# PA2_PMIC.net
KiCad netlist of a schematic drawn in Altium Designer
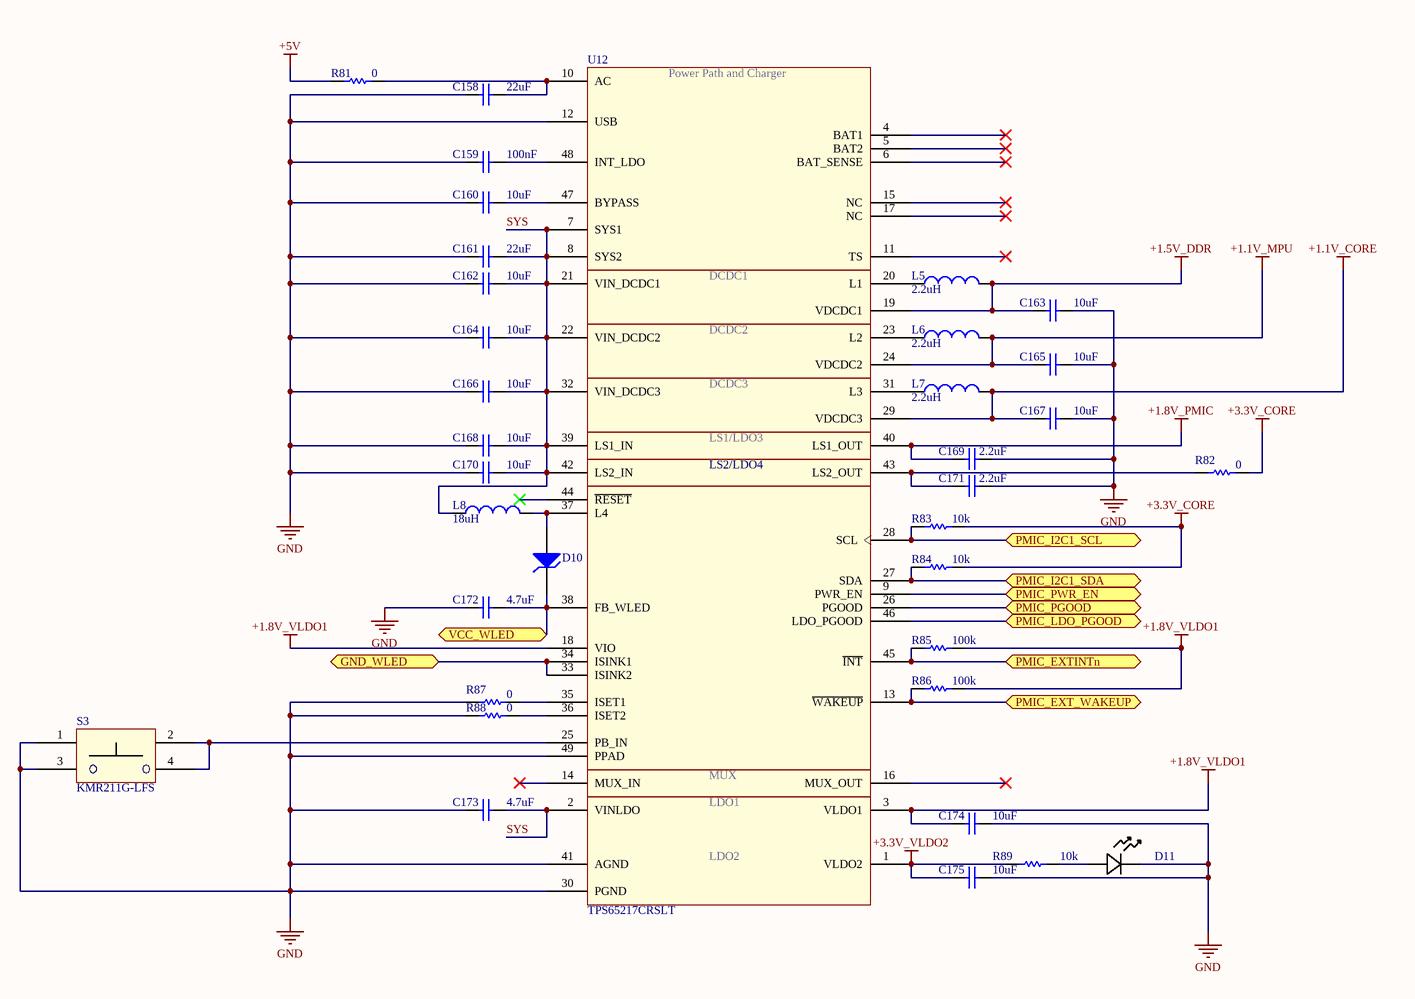
[diagram p0: PA2_PMIC.SchDoc]

(export (version "E")
  (design (tool "Eeschema 10.0.6"))
  (components
    (comp (ref "C158")
      (value "22uF")
      (footprint "CAPC1608X08")
      (description "Capacitor")
      (fields (field (name "Comment") "Cap 22uF"))
      (libsource (lib "Michel") (part "Cap"))
    )
    (comp (ref "C159")
      (value "100nF")
      (footprint "CAPC1608X08")
      (description "Capacitor")
      (fields (field (name "Comment") "Cap 100nF"))
      (libsource (lib "Michel") (part "Cap"))
    )
    (comp (ref "C160")
      (value "10uF")
      (footprint "CAPC1608X08")
      (description "Capacitor")
      (fields (field (name "Comment") "Cap 10uF"))
      (libsource (lib "Michel") (part "Cap"))
    )
    (comp (ref "C161")
      (value "22uF")
      (footprint "CAPC1608X08")
      (description "Capacitor")
      (fields (field (name "Comment") "Cap 22uF"))
      (libsource (lib "Michel") (part "Cap"))
    )
    (comp (ref "C162")
      (value "10uF")
      (footprint "CAPC1608X08")
      (description "Capacitor")
      (fields (field (name "Comment") "Cap 10uF"))
      (libsource (lib "Michel") (part "Cap"))
    )
    (comp (ref "C163")
      (value "10uF")
      (footprint "CAPC1608X08")
      (description "Capacitor")
      (fields (field (name "Comment") "Cap 10uF"))
      (libsource (lib "Michel") (part "Cap"))
    )
    (comp (ref "C164")
      (value "10uF")
      (footprint "CAPC1608X08")
      (description "Capacitor")
      (fields (field (name "Comment") "Cap 10uF"))
      (libsource (lib "Michel") (part "Cap"))
    )
    (comp (ref "C165")
      (value "10uF")
      (footprint "CAPC1608X08")
      (description "Capacitor")
      (fields (field (name "Comment") "Cap 10uF"))
      (libsource (lib "Michel") (part "Cap"))
    )
    (comp (ref "C166")
      (value "10uF")
      (footprint "CAPC1608X08")
      (description "Capacitor")
      (fields (field (name "Comment") "Cap 10uF"))
      (libsource (lib "Michel") (part "Cap"))
    )
    (comp (ref "C167")
      (value "10uF")
      (footprint "CAPC1608X08")
      (description "Capacitor")
      (fields (field (name "Comment") "Cap 10uF"))
      (libsource (lib "Michel") (part "Cap"))
    )
    (comp (ref "C168")
      (value "10uF")
      (footprint "CAPC1608X08")
      (description "Capacitor")
      (fields (field (name "Comment") "Cap 10uF"))
      (libsource (lib "Michel") (part "Cap"))
    )
    (comp (ref "C169")
      (value "2.2uF")
      (footprint "CAPC1608X08")
      (description "Capacitor")
      (fields (field (name "Comment") "Cap 2.2uF"))
      (libsource (lib "Michel") (part "Cap"))
    )
    (comp (ref "C170")
      (value "10uF")
      (footprint "CAPC1608X08")
      (description "Capacitor")
      (fields (field (name "Comment") "Cap 10uF"))
      (libsource (lib "Michel") (part "Cap"))
    )
    (comp (ref "C171")
      (value "2.2uF")
      (footprint "CAPC1608X08")
      (description "Capacitor")
      (fields (field (name "Comment") "Cap 2.2uF"))
      (libsource (lib "Michel") (part "Cap"))
    )
    (comp (ref "C172")
      (value "4.7uF")
      (footprint "CAPC1608X08")
      (description "Capacitor")
      (fields (field (name "Comment") "Cap 4.7uF"))
      (libsource (lib "Michel") (part "Cap"))
    )
    (comp (ref "C173")
      (value "4.7uF")
      (footprint "CAPC1608X08")
      (description "Capacitor")
      (fields (field (name "Comment") "Cap 4.7uF"))
      (libsource (lib "Michel") (part "Cap"))
    )
    (comp (ref "C174")
      (value "10uF")
      (footprint "CAPC1608X08")
      (description "Capacitor")
      (fields (field (name "Comment") "Cap 10uF"))
      (libsource (lib "Michel") (part "Cap"))
    )
    (comp (ref "C175")
      (value "10uF")
      (footprint "CAPC1608X08")
      (description "Capacitor")
      (fields (field (name "Comment") "Cap 10uF"))
      (libsource (lib "Michel") (part "Cap"))
    )
    (comp (ref "D10")
      (value "D Zener")
      (footprint "MF03A-M")
      (description "Zener Diode")
      (libsource (lib "Michel") (part "D Zener"))
    )
    (comp (ref "D11")
      (value "Blanc")
      (footprint "LED_LNJ")
      (description "LED Blanc")
      (libsource (lib "Michel") (part "LNJ037X8ARA"))
    )
    (comp (ref "L5")
      (value "2.2uH")
      (footprint "INDM1608X08N")
      (description "Inductor")
      (libsource (lib "Michel") (part "Inductor"))
    )
    (comp (ref "L6")
      (value "2.2uH")
      (footprint "INDM1608X08N")
      (description "Inductor")
      (libsource (lib "Michel") (part "Inductor"))
    )
    (comp (ref "L7")
      (value "2.2uH")
      (footprint "INDM1608X08N")
      (description "Inductor")
      (libsource (lib "Michel") (part "Inductor"))
    )
    (comp (ref "L8")
      (value "18uH")
      (footprint "INDM2612X12N")
      (description "Inductor")
      (libsource (lib "Michel") (part "Inductor"))
    )
    (comp (ref "R81")
      (value "0")
      (footprint "RESC1608X05")
      (description "Resistor")
      (fields (field (name "Comment") "Res 0 Ohm"))
      (libsource (lib "Michel") (part "Res1"))
    )
    (comp (ref "R82")
      (value "0")
      (footprint "RESC1608X05")
      (description "Resistor")
      (fields (field (name "Comment") "Res 0 Ohm"))
      (libsource (lib "Michel") (part "Res1"))
    )
    (comp (ref "R83")
      (value "10k")
      (footprint "RESC1608X05")
      (description "Resistor")
      (fields (field (name "Comment") "Res 10k"))
      (libsource (lib "Michel") (part "Res1"))
    )
    (comp (ref "R84")
      (value "10k")
      (footprint "RESC1608X05")
      (description "Resistor")
      (fields (field (name "Comment") "Res 10k"))
      (libsource (lib "Michel") (part "Res1"))
    )
    (comp (ref "R85")
      (value "100k")
      (footprint "RESC1608X05")
      (description "Resistor")
      (fields (field (name "Comment") "Res 100k"))
      (libsource (lib "Michel") (part "Res1"))
    )
    (comp (ref "R86")
      (value "100k")
      (footprint "RESC1608X05")
      (description "Resistor")
      (fields (field (name "Comment") "Res 100k"))
      (libsource (lib "Michel") (part "Res1"))
    )
    (comp (ref "R87")
      (value "0")
      (footprint "RESC1608X05")
      (description "Resistor")
      (fields (field (name "Comment") "Res 0 Ohm"))
      (libsource (lib "Michel") (part "Res1"))
    )
    (comp (ref "R88")
      (value "0")
      (footprint "RESC1608X05")
      (description "Resistor")
      (fields (field (name "Comment") "Res 0 Ohm"))
      (libsource (lib "Michel") (part "Res1"))
    )
    (comp (ref "R89")
      (value "10k")
      (footprint "RESC1608X05")
      (description "Resistor")
      (fields (field (name "Comment") "Res 10k"))
      (libsource (lib "Michel") (part "Res1"))
    )
    (comp (ref "S3")
      (value "KMR211G-LFS")
      (footprint "C&K_KMR211G")
      (description "Commutateur tactile")
      (libsource (lib "Michel") (part "KMR211G-LFS"))
    )
    (comp (ref "U12")
      (value "TPS65217CRSLT")
      (footprint "CRSLT")
      (description "Gestion d'alimentation PMIC")
      (libsource (lib "Michel") (part "TPS65217CRSLT"))
    )
  )
  (nets
    (net (code "1") (name "+1.1V_CORE") (class "Default")
      (node (ref "C167") (pin "1") (pinfunction "1_1") (pintype "passive"))
      (node (ref "L7") (pin "2") (pinfunction "2_2") (pintype "passive"))
      (node (ref "U12") (pin "29") (pinfunction "VDCDC3_29") (pintype "passive"))
    )
    (net (code "2") (name "+1.1V_MPU") (class "Default")
      (node (ref "C165") (pin "1") (pinfunction "1_1") (pintype "passive"))
      (node (ref "L6") (pin "2") (pinfunction "2_2") (pintype "passive"))
      (node (ref "U12") (pin "24") (pinfunction "VDCDC2_24") (pintype "passive"))
    )
    (net (code "3") (name "+1.5V_DDR") (class "Default")
      (node (ref "C163") (pin "1") (pinfunction "1_1") (pintype "passive"))
      (node (ref "L5") (pin "2") (pinfunction "2_2") (pintype "passive"))
      (node (ref "U12") (pin "19") (pinfunction "VDCDC1_19") (pintype "passive"))
    )
    (net (code "4") (name "+1.8V_PMIC") (class "Default")
      (node (ref "C169") (pin "2") (pinfunction "2_2") (pintype "passive"))
      (node (ref "U12") (pin "40") (pinfunction "LS1_OUT_40") (pintype "passive"))
    )
    (net (code "5") (name "+1.8V_VLDO1") (class "Default")
      (node (ref "C174") (pin "1") (pinfunction "1_1") (pintype "passive"))
      (node (ref "R85") (pin "2") (pinfunction "2_2") (pintype "passive"))
      (node (ref "R86") (pin "2") (pinfunction "2_2") (pintype "passive"))
      (node (ref "U12") (pin "18") (pinfunction "VIO_18") (pintype "passive"))
      (node (ref "U12") (pin "3") (pinfunction "VLDO1_3") (pintype "passive"))
    )
    (net (code "6") (name "+3.3V_CORE") (class "Default")
      (node (ref "R82") (pin "2") (pinfunction "2_2") (pintype "passive"))
      (node (ref "R83") (pin "2") (pinfunction "2_2") (pintype "passive"))
      (node (ref "R84") (pin "2") (pinfunction "2_2") (pintype "passive"))
    )
    (net (code "7") (name "+3.3V_VLDO2") (class "Default")
      (node (ref "C175") (pin "1") (pinfunction "1_1") (pintype "passive"))
      (node (ref "R89") (pin "1") (pinfunction "1_1") (pintype "passive"))
      (node (ref "U12") (pin "1") (pinfunction "VLDO2_1") (pintype "passive"))
    )
    (net (code "8") (name "+5V") (class "Default")
      (node (ref "R81") (pin "1") (pinfunction "1_1") (pintype "passive"))
    )
    (net (code "9") (name "/GND_WLED") (class "Default")
      (node (ref "U12") (pin "33") (pinfunction "ISINK2_33") (pintype "passive"))
      (node (ref "U12") (pin "34") (pinfunction "ISINK1_34") (pintype "passive"))
    )
    (net (code "10") (name "/PMIC_EXTINTn") (class "Default")
      (node (ref "R85") (pin "1") (pinfunction "1_1") (pintype "passive"))
      (node (ref "U12") (pin "45") (pinfunction "~{INT}_45") (pintype "passive"))
    )
    (net (code "11") (name "/PMIC_EXT_WAKEUP") (class "Default")
      (node (ref "R86") (pin "1") (pinfunction "1_1") (pintype "passive"))
      (node (ref "U12") (pin "13") (pinfunction "~{WAKEUP}_13") (pintype "passive"))
    )
    (net (code "12") (name "/PMIC_I2C1_SCL") (class "Default")
      (node (ref "R83") (pin "1") (pinfunction "1_1") (pintype "passive"))
      (node (ref "U12") (pin "28") (pinfunction "SCL_28") (pintype "passive"))
    )
    (net (code "13") (name "/PMIC_I2C1_SDA") (class "Default")
      (node (ref "R84") (pin "1") (pinfunction "1_1") (pintype "passive"))
      (node (ref "U12") (pin "27") (pinfunction "SDA_27") (pintype "passive"))
    )
    (net (code "14") (name "/PMIC_LDO_PGOOD") (class "Default")
      (node (ref "U12") (pin "46") (pinfunction "LDO_PGOOD_46") (pintype "passive"))
    )
    (net (code "15") (name "/PMIC_PGOOD") (class "Default")
      (node (ref "U12") (pin "26") (pinfunction "PGOOD_26") (pintype "passive"))
    )
    (net (code "16") (name "/PMIC_PWR_EN") (class "Default")
      (node (ref "U12") (pin "9") (pinfunction "PWR_EN_9") (pintype "passive"))
    )
    (net (code "17") (name "/SYS") (class "Default")
      (node (ref "C161") (pin "2") (pinfunction "2_2") (pintype "passive"))
      (node (ref "C162") (pin "2") (pinfunction "2_2") (pintype "passive"))
      (node (ref "C164") (pin "2") (pinfunction "2_2") (pintype "passive"))
      (node (ref "C166") (pin "2") (pinfunction "2_2") (pintype "passive"))
      (node (ref "C168") (pin "2") (pinfunction "2_2") (pintype "passive"))
      (node (ref "C170") (pin "2") (pinfunction "2_2") (pintype "passive"))
      (node (ref "C173") (pin "2") (pinfunction "2_2") (pintype "passive"))
      (node (ref "L8") (pin "1") (pinfunction "1_1") (pintype "passive"))
      (node (ref "U12") (pin "2") (pinfunction "VINLDO_2") (pintype "passive"))
      (node (ref "U12") (pin "21") (pinfunction "VIN_DCDC1_21") (pintype "passive"))
      (node (ref "U12") (pin "22") (pinfunction "VIN_DCDC2_22") (pintype "passive"))
      (node (ref "U12") (pin "32") (pinfunction "VIN_DCDC3_32") (pintype "passive"))
      (node (ref "U12") (pin "39") (pinfunction "LS1_IN_39") (pintype "passive"))
      (node (ref "U12") (pin "42") (pinfunction "LS2_IN_42") (pintype "passive"))
      (node (ref "U12") (pin "7") (pinfunction "SYS1_7") (pintype "passive"))
      (node (ref "U12") (pin "8") (pinfunction "SYS2_8") (pintype "passive"))
    )
    (net (code "18") (name "/VCC_WLED") (class "Default")
      (node (ref "C172") (pin "2") (pinfunction "2_2") (pintype "passive"))
      (node (ref "D10") (pin "2") (pinfunction "K_2") (pintype "passive"))
      (node (ref "U12") (pin "38") (pinfunction "FB_WLED_38") (pintype "passive"))
    )
    (net (code "19") (name "GND") (class "Default")
      (node (ref "C158") (pin "1") (pinfunction "1_1") (pintype "passive"))
      (node (ref "C159") (pin "1") (pinfunction "1_1") (pintype "passive"))
      (node (ref "C160") (pin "1") (pinfunction "1_1") (pintype "passive"))
      (node (ref "C161") (pin "1") (pinfunction "1_1") (pintype "passive"))
      (node (ref "C162") (pin "1") (pinfunction "1_1") (pintype "passive"))
      (node (ref "C163") (pin "2") (pinfunction "2_2") (pintype "passive"))
      (node (ref "C164") (pin "1") (pinfunction "1_1") (pintype "passive"))
      (node (ref "C165") (pin "2") (pinfunction "2_2") (pintype "passive"))
      (node (ref "C166") (pin "1") (pinfunction "1_1") (pintype "passive"))
      (node (ref "C167") (pin "2") (pinfunction "2_2") (pintype "passive"))
      (node (ref "C168") (pin "1") (pinfunction "1_1") (pintype "passive"))
      (node (ref "C169") (pin "1") (pinfunction "1_1") (pintype "passive"))
      (node (ref "C170") (pin "1") (pinfunction "1_1") (pintype "passive"))
      (node (ref "C171") (pin "1") (pinfunction "1_1") (pintype "passive"))
      (node (ref "C172") (pin "1") (pinfunction "1_1") (pintype "passive"))
      (node (ref "C173") (pin "1") (pinfunction "1_1") (pintype "passive"))
      (node (ref "C174") (pin "2") (pinfunction "2_2") (pintype "passive"))
      (node (ref "C175") (pin "2") (pinfunction "2_2") (pintype "passive"))
      (node (ref "D11") (pin "1") (pinfunction "1_1") (pintype "passive"))
      (node (ref "R87") (pin "1") (pinfunction "1_1") (pintype "passive"))
      (node (ref "R88") (pin "1") (pinfunction "1_1") (pintype "passive"))
      (node (ref "S3") (pin "1") (pinfunction "1_1") (pintype "passive"))
      (node (ref "S3") (pin "3") (pinfunction "3_3") (pintype "passive"))
      (node (ref "U12") (pin "12") (pinfunction "USB_12") (pintype "passive"))
      (node (ref "U12") (pin "30") (pinfunction "PGND_30") (pintype "passive"))
      (node (ref "U12") (pin "41") (pinfunction "AGND_41") (pintype "passive"))
      (node (ref "U12") (pin "49") (pinfunction "PPAD_49") (pintype "passive"))
    )
    (net (code "20") (name "Net-(D10-A)") (class "Default")
      (node (ref "D10") (pin "1") (pinfunction "A_1") (pintype "passive"))
      (node (ref "L8") (pin "2") (pinfunction "2_2") (pintype "passive"))
      (node (ref "U12") (pin "37") (pinfunction "L4_37") (pintype "passive"))
    )
    (net (code "21") (name "Net-(D11-Pad2)") (class "Default")
      (node (ref "D11") (pin "2") (pinfunction "2_2") (pintype "passive"))
      (node (ref "R89") (pin "2") (pinfunction "2_2") (pintype "passive"))
    )
    (net (code "22") (name "Net-(U12-AC)") (class "Default")
      (node (ref "C158") (pin "2") (pinfunction "2_2") (pintype "passive"))
      (node (ref "R81") (pin "2") (pinfunction "2_2") (pintype "passive"))
      (node (ref "U12") (pin "10") (pinfunction "AC_10") (pintype "passive"))
    )
    (net (code "23") (name "Net-(U12-BYPASS)") (class "Default")
      (node (ref "C160") (pin "2") (pinfunction "2_2") (pintype "passive"))
      (node (ref "U12") (pin "47") (pinfunction "BYPASS_47") (pintype "passive"))
    )
    (net (code "24") (name "Net-(U12-INT_LDO)") (class "Default")
      (node (ref "C159") (pin "2") (pinfunction "2_2") (pintype "passive"))
      (node (ref "U12") (pin "48") (pinfunction "INT_LDO_48") (pintype "passive"))
    )
    (net (code "25") (name "Net-(U12-ISET1)") (class "Default")
      (node (ref "R87") (pin "2") (pinfunction "2_2") (pintype "passive"))
      (node (ref "U12") (pin "35") (pinfunction "ISET1_35") (pintype "passive"))
    )
    (net (code "26") (name "Net-(U12-ISET2)") (class "Default")
      (node (ref "R88") (pin "2") (pinfunction "2_2") (pintype "passive"))
      (node (ref "U12") (pin "36") (pinfunction "ISET2_36") (pintype "passive"))
    )
    (net (code "27") (name "Net-(U12-L1)") (class "Default")
      (node (ref "L5") (pin "1") (pinfunction "1_1") (pintype "passive"))
      (node (ref "U12") (pin "20") (pinfunction "L1_20") (pintype "passive"))
    )
    (net (code "28") (name "Net-(U12-L2)") (class "Default")
      (node (ref "L6") (pin "1") (pinfunction "1_1") (pintype "passive"))
      (node (ref "U12") (pin "23") (pinfunction "L2_23") (pintype "passive"))
    )
    (net (code "29") (name "Net-(U12-L3)") (class "Default")
      (node (ref "L7") (pin "1") (pinfunction "1_1") (pintype "passive"))
      (node (ref "U12") (pin "31") (pinfunction "L3_31") (pintype "passive"))
    )
    (net (code "30") (name "Net-(U12-LS2_OUT)") (class "Default")
      (node (ref "C171") (pin "2") (pinfunction "2_2") (pintype "passive"))
      (node (ref "R82") (pin "1") (pinfunction "1_1") (pintype "passive"))
      (node (ref "U12") (pin "43") (pinfunction "LS2_OUT_43") (pintype "passive"))
    )
    (net (code "31") (name "Net-(U12-PB_IN)") (class "Default")
      (node (ref "S3") (pin "2") (pinfunction "2_2") (pintype "passive"))
      (node (ref "S3") (pin "4") (pinfunction "4_4") (pintype "passive"))
      (node (ref "U12") (pin "25") (pinfunction "PB_IN_25") (pintype "passive"))
    )
    (net (code "32") (name "unconnected-(U12-BAT1-Pad4)") (class "Default")
      (node (ref "U12") (pin "4") (pinfunction "BAT1_4") (pintype "passive+no_connect"))
    )
    (net (code "33") (name "unconnected-(U12-BAT2-Pad5)") (class "Default")
      (node (ref "U12") (pin "5") (pinfunction "BAT2_5") (pintype "passive+no_connect"))
    )
    (net (code "34") (name "unconnected-(U12-BAT_SENSE-Pad6)") (class "Default")
      (node (ref "U12") (pin "6") (pinfunction "BAT_SENSE_6") (pintype "passive+no_connect"))
    )
    (net (code "35") (name "unconnected-(U12-MUX_IN-Pad14)") (class "Default")
      (node (ref "U12") (pin "14") (pinfunction "MUX_IN_14") (pintype "passive+no_connect"))
    )
    (net (code "36") (name "unconnected-(U12-MUX_OUT-Pad16)") (class "Default")
      (node (ref "U12") (pin "16") (pinfunction "MUX_OUT_16") (pintype "passive+no_connect"))
    )
    (net (code "37") (name "unconnected-(U12-NC-Pad15)") (class "Default")
      (node (ref "U12") (pin "15") (pinfunction "NC_15") (pintype "passive+no_connect"))
    )
    (net (code "38") (name "unconnected-(U12-NC-Pad17)") (class "Default")
      (node (ref "U12") (pin "17") (pinfunction "NC_17") (pintype "passive+no_connect"))
    )
    (net (code "39") (name "unconnected-(U12-TS-Pad11)") (class "Default")
      (node (ref "U12") (pin "11") (pinfunction "TS_11") (pintype "passive+no_connect"))
    )
    (net (code "40") (name "unconnected-(U12-~{RESET}-Pad44)") (class "Default")
      (node (ref "U12") (pin "44") (pinfunction "~{RESET}_44") (pintype "passive+no_connect"))
    )
  )
)
